# Sheet_02_Arduino_Mega2560.net
KiCad netlist of a schematic drawn in Altium Designer
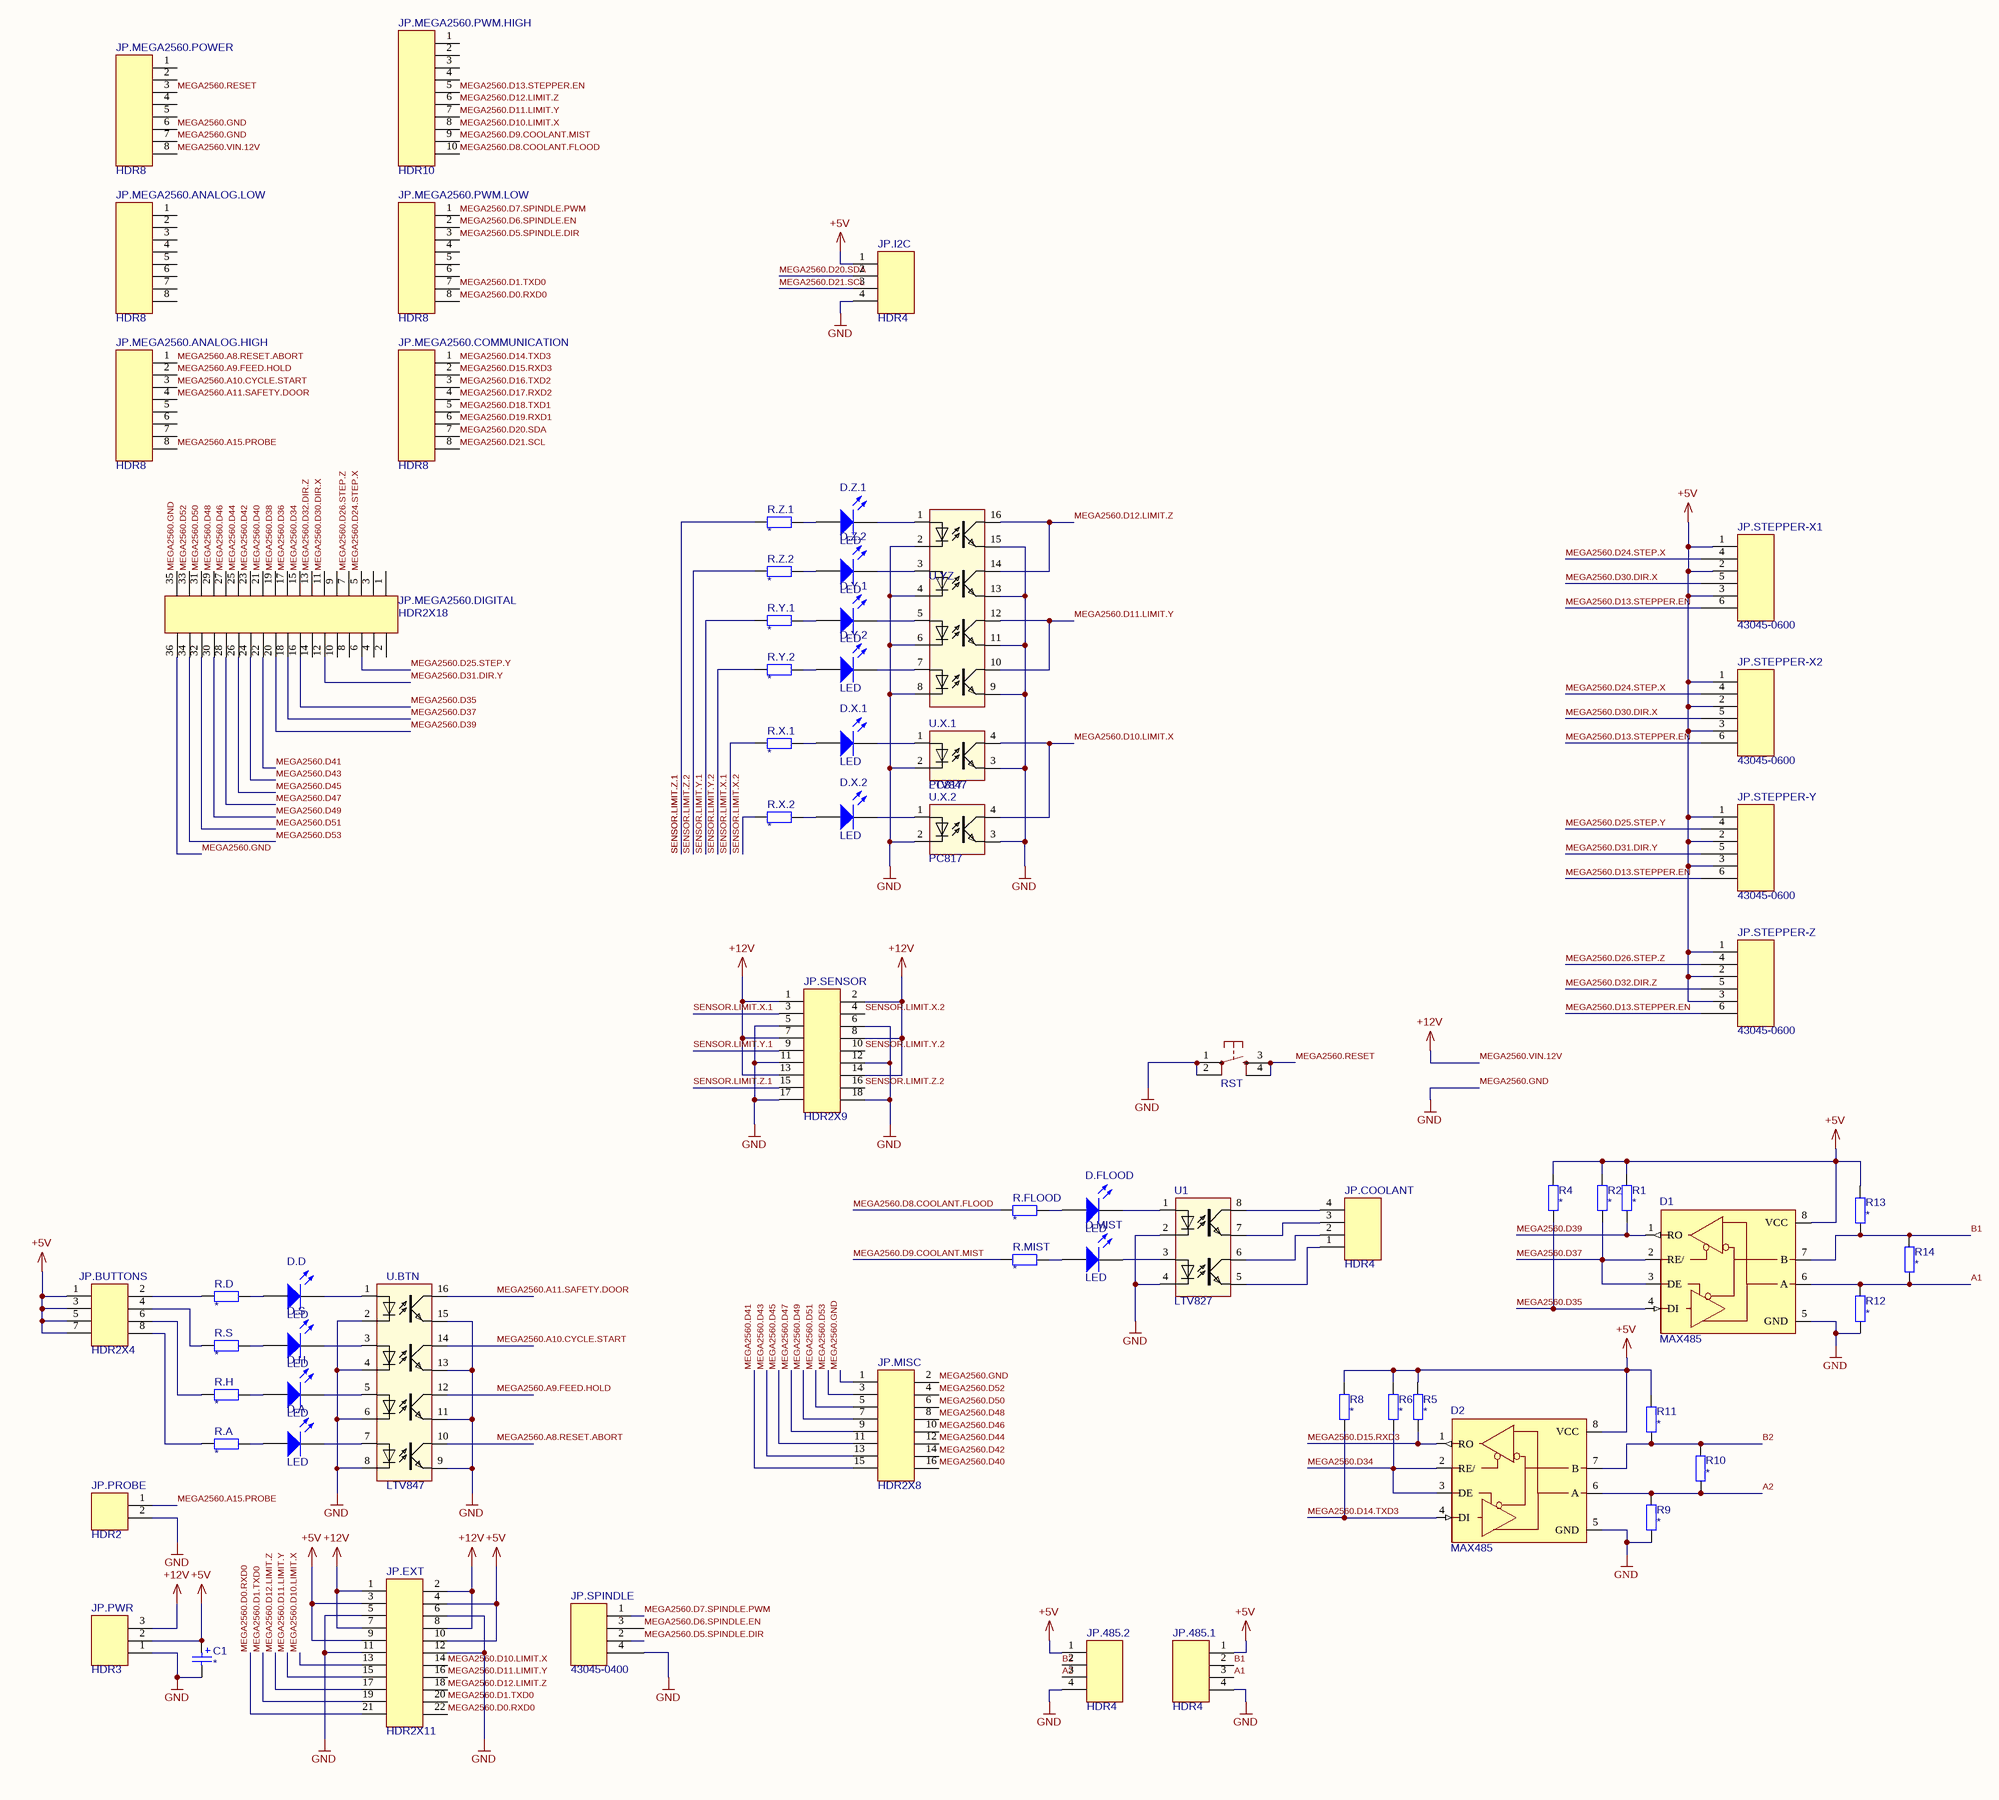
[diagram p0: Sheet.02.Arduino.Mega2560.SchDoc]

(export (version "E")
  (design (tool "Eeschema 10.0.6"))
  (components
    (comp (ref "C1")
      (value "*")
      (footprint "E3,5-8")
      (description "Polarized Capacitor (Radial)")
      (fields (field (name "PUBLISHER") "Altium Limited"))
      (libsource (lib "Net173") (part "CAP.POL"))
    )
    (comp (ref "D.A")
      (value "LED")
      (footprint "1206-SMD-LED")
      (fields (field (name "PUBLISHER") "Altium Limited"))
      (libsource (lib "Net173") (part "LED"))
    )
    (comp (ref "D.D")
      (value "LED")
      (footprint "1206-SMD-LED")
      (fields (field (name "PUBLISHER") "Altium Limited"))
      (libsource (lib "Net173") (part "LED"))
    )
    (comp (ref "D.FLOOD")
      (value "LED")
      (footprint "1206-SMD-LED")
      (fields (field (name "PUBLISHER") "Altium Limited"))
      (libsource (lib "Net173") (part "LED"))
    )
    (comp (ref "D.H")
      (value "LED")
      (footprint "1206-SMD-LED")
      (fields (field (name "PUBLISHER") "Altium Limited"))
      (libsource (lib "Net173") (part "LED"))
    )
    (comp (ref "D.MIST")
      (value "LED")
      (footprint "1206-SMD-LED")
      (fields (field (name "PUBLISHER") "Altium Limited"))
      (libsource (lib "Net173") (part "LED"))
    )
    (comp (ref "D.S")
      (value "LED")
      (footprint "1206-SMD-LED")
      (fields (field (name "PUBLISHER") "Altium Limited"))
      (libsource (lib "Net173") (part "LED"))
    )
    (comp (ref "D.X.1")
      (value "LED")
      (footprint "1206-SMD-LED")
      (fields (field (name "PUBLISHER") "Altium Limited"))
      (libsource (lib "Net173") (part "LED"))
    )
    (comp (ref "D.X.2")
      (value "LED")
      (footprint "1206-SMD-LED")
      (fields (field (name "PUBLISHER") "Altium Limited"))
      (libsource (lib "Net173") (part "LED"))
    )
    (comp (ref "D.Y.1")
      (value "LED")
      (footprint "1206-SMD-LED")
      (fields (field (name "PUBLISHER") "Altium Limited"))
      (libsource (lib "Net173") (part "LED"))
    )
    (comp (ref "D.Y.2")
      (value "LED")
      (footprint "1206-SMD-LED")
      (fields (field (name "PUBLISHER") "Altium Limited"))
      (libsource (lib "Net173") (part "LED"))
    )
    (comp (ref "D.Z.1")
      (value "LED")
      (footprint "1206-SMD-LED")
      (fields (field (name "PUBLISHER") "Altium Limited"))
      (libsource (lib "Net173") (part "LED"))
    )
    (comp (ref "D.Z.2")
      (value "LED")
      (footprint "1206-SMD-LED")
      (fields (field (name "PUBLISHER") "Altium Limited"))
      (libsource (lib "Net173") (part "LED"))
    )
    (comp (ref "D1") (value "MAX485") (footprint "DIP8") (libsource (lib "Net173") (part "MAX485")))
    (comp (ref "D2") (value "MAX485") (footprint "DIP8") (libsource (lib "Net173") (part "MAX485")))
    (comp (ref "JP.485.1") (value "HDR4") (footprint "HDR1X4") (libsource (lib "") (part "HDR4_2")))
    (comp (ref "JP.485.2") (value "HDR4") (footprint "HDR1X4") (libsource (lib "Net173") (part "HDR4")))
    (comp (ref "JP.BUTTONS") (value "HDR2X4") (footprint "HDR2X4") (libsource (lib "Net173") (part "HDR2X4")))
    (comp (ref "JP.COOLANT") (value "HDR4") (footprint "HDR1X4H") (libsource (lib "") (part "HDR4_1")))
    (comp (ref "JP.EXT") (value "HDR2X11") (footprint "HDR2X11") (libsource (lib "Net173") (part "HDR2X11")))
    (comp (ref "JP.I2C") (value "HDR4") (footprint "HDR1X4") (libsource (lib "Net173") (part "HDR4")))
    (comp (ref "JP.MEGA2560.ANALOG.HIGH")
      (value "HDR8")
      (footprint "HDR8-BOTTOM")
      (libsource (lib "Net173") (part "HDR8"))
    )
    (comp (ref "JP.MEGA2560.ANALOG.LOW")
      (value "HDR8")
      (footprint "HDR8-BOTTOM")
      (libsource (lib "Net173") (part "HDR8"))
    )
    (comp (ref "JP.MEGA2560.COMMUNICATION")
      (value "HDR8")
      (footprint "HDR8-BOTTOM")
      (libsource (lib "Net173") (part "HDR8"))
    )
    (comp (ref "JP.MEGA2560.DIGITAL")
      (value "HDR2X18")
      (footprint "HDR2X18-BOTTOM")
      (libsource (lib "Net173") (part "HDR2X18"))
    )
    (comp (ref "JP.MEGA2560.POWER")
      (value "HDR8")
      (footprint "HDR8-BOTTOM")
      (libsource (lib "Net173") (part "HDR8"))
    )
    (comp (ref "JP.MEGA2560.PWM.HIGH")
      (value "HDR10")
      (footprint "HDR10-BOTTOM")
      (libsource (lib "Net173") (part "HDR10"))
    )
    (comp (ref "JP.MEGA2560.PWM.LOW")
      (value "HDR8")
      (footprint "HDR8-BOTTOM")
      (libsource (lib "Net173") (part "HDR8"))
    )
    (comp (ref "JP.MISC") (value "HDR2X8") (footprint "HDR2X8") (libsource (lib "Net173") (part "HDR2X8")))
    (comp (ref "JP.PROBE") (value "HDR2") (footprint "HDR1X2") (libsource (lib "Net173") (part "HDR2")))
    (comp (ref "JP.PWR") (value "HDR3") (footprint "HDR1X3H") (libsource (lib "Net173") (part "HDR3")))
    (comp (ref "JP.SENSOR") (value "HDR2X9") (footprint "HDR2X9") (libsource (lib "Net173") (part "HDR2X9")))
    (comp (ref "JP.SPINDLE")
      (value "43045-0400")
      (footprint "43045-0400")
      (libsource (lib "Net173") (part "43045-0400"))
    )
    (comp (ref "JP.STEPPER-X1")
      (value "43045-0600")
      (footprint "43045-0600")
      (libsource (lib "Net173") (part "43045-0600"))
    )
    (comp (ref "JP.STEPPER-X2")
      (value "43045-0600")
      (footprint "43045-0600")
      (libsource (lib "Net173") (part "43045-0600"))
    )
    (comp (ref "JP.STEPPER-Y")
      (value "43045-0600")
      (footprint "43045-0600")
      (libsource (lib "Net173") (part "43045-0600"))
    )
    (comp (ref "JP.STEPPER-Z")
      (value "43045-0600")
      (footprint "43045-0600")
      (libsource (lib "Net173") (part "43045-0600"))
    )
    (comp (ref "R.A") (value "*") (footprint "1206-SMD-RES") (libsource (lib "") (part "RES_1")))
    (comp (ref "R.D") (value "*") (footprint "1206-SMD-RES") (libsource (lib "") (part "RES_1")))
    (comp (ref "R.FLOOD") (value "*") (footprint "1206-SMD-RES") (libsource (lib "") (part "RES_1")))
    (comp (ref "R.H") (value "*") (footprint "1206-SMD-RES") (libsource (lib "") (part "RES_1")))
    (comp (ref "R.MIST") (value "*") (footprint "1206-SMD-RES") (libsource (lib "") (part "RES_1")))
    (comp (ref "R.S") (value "*") (footprint "1206-SMD-RES") (libsource (lib "") (part "RES_1")))
    (comp (ref "R.X.1") (value "*") (footprint "1206-SMD-RES") (libsource (lib "") (part "RES_1")))
    (comp (ref "R.X.2") (value "*") (footprint "1206-SMD-RES") (libsource (lib "") (part "RES_1")))
    (comp (ref "R.Y.1") (value "*") (footprint "1206-SMD-RES") (libsource (lib "") (part "RES_1")))
    (comp (ref "R.Y.2") (value "*") (footprint "1206-SMD-RES") (libsource (lib "") (part "RES_1")))
    (comp (ref "R.Z.1") (value "*") (footprint "1206-SMD-RES") (libsource (lib "") (part "RES_1")))
    (comp (ref "R.Z.2") (value "*") (footprint "1206-SMD-RES") (libsource (lib "") (part "RES_1")))
    (comp (ref "R1") (value "*") (footprint "1206-SMD-RES") (libsource (lib "Net173") (part "RES")))
    (comp (ref "R2") (value "*") (footprint "1206-SMD-RES") (libsource (lib "Net173") (part "RES")))
    (comp (ref "R4") (value "*") (footprint "1206-SMD-RES") (libsource (lib "Net173") (part "RES")))
    (comp (ref "R5") (value "*") (footprint "1206-SMD-RES") (libsource (lib "Net173") (part "RES")))
    (comp (ref "R6") (value "*") (footprint "1206-SMD-RES") (libsource (lib "Net173") (part "RES")))
    (comp (ref "R8") (value "*") (footprint "1206-SMD-RES") (libsource (lib "Net173") (part "RES")))
    (comp (ref "R9") (value "*") (footprint "1206-SMD-RES") (libsource (lib "Net173") (part "RES")))
    (comp (ref "R10") (value "*") (footprint "1206-SMD-RES") (libsource (lib "Net173") (part "RES")))
    (comp (ref "R11") (value "*") (footprint "1206-SMD-RES") (libsource (lib "Net173") (part "RES")))
    (comp (ref "R12") (value "*") (footprint "1206-SMD-RES") (libsource (lib "Net173") (part "RES")))
    (comp (ref "R13") (value "*") (footprint "1206-SMD-RES") (libsource (lib "Net173") (part "RES")))
    (comp (ref "R14") (value "*") (footprint "1206-SMD-RES") (libsource (lib "Net173") (part "RES")))
    (comp (ref "RST")
      (value "OMRON SWITCH")
      (footprint "B3F-10XX")
      (fields (field (name "MPN") "B3F-1000"))
      (libsource (lib "Net173") (part "B3F-10-XX"))
    )
    (comp (ref "U.BTN") (value "LTV847") (footprint "DIP16") (libsource (lib "Net173") (part "LTV847")))
    (comp (ref "U.X.1") (value "PC817") (footprint "DIP4") (libsource (lib "Net173") (part "PC817")))
    (comp (ref "U.X.2") (value "PC817") (footprint "DIP4") (libsource (lib "Net173") (part "PC817")))
    (comp (ref "U.YZ") (value "LTV847") (footprint "DIP16") (libsource (lib "Net173") (part "LTV847")))
    (comp (ref "U1") (value "LTV827") (footprint "DIP8") (libsource (lib "Net173") (part "LTV827")))
  )
  (nets
    (net (code "1") (name "+5V") (class "Default")
      (node (ref "C1") (pin "+") (pinfunction "1_+") (pintype "passive"))
      (node (ref "D1") (pin "8") (pinfunction "VCC_8") (pintype "power_in"))
      (node (ref "D2") (pin "8") (pinfunction "VCC_8") (pintype "power_in"))
      (node (ref "JP.485.1") (pin "1") (pinfunction "1_1") (pintype "passive"))
      (node (ref "JP.485.2") (pin "1") (pinfunction "1_1") (pintype "passive"))
      (node (ref "JP.BUTTONS") (pin "1") (pinfunction "1_1") (pintype "passive"))
      (node (ref "JP.BUTTONS") (pin "3") (pinfunction "3_3") (pintype "passive"))
      (node (ref "JP.BUTTONS") (pin "5") (pinfunction "5_5") (pintype "passive"))
      (node (ref "JP.BUTTONS") (pin "7") (pinfunction "7_7") (pintype "passive"))
      (node (ref "JP.EXT") (pin "10") (pinfunction "10_10") (pintype "passive"))
      (node (ref "JP.EXT") (pin "3") (pinfunction "3_3") (pintype "passive"))
      (node (ref "JP.EXT") (pin "4") (pinfunction "4_4") (pintype "passive"))
      (node (ref "JP.EXT") (pin "9") (pinfunction "9_9") (pintype "passive"))
      (node (ref "JP.I2C") (pin "1") (pinfunction "1_1") (pintype "passive"))
      (node (ref "JP.PWR") (pin "2") (pinfunction "2_2") (pintype "passive"))
      (node (ref "JP.STEPPER-X1") (pin "1") (pinfunction "1_1") (pintype "passive"))
      (node (ref "JP.STEPPER-X1") (pin "2") (pinfunction "2_2") (pintype "passive"))
      (node (ref "JP.STEPPER-X1") (pin "3") (pinfunction "3_3") (pintype "passive"))
      (node (ref "JP.STEPPER-X2") (pin "1") (pinfunction "1_1") (pintype "passive"))
      (node (ref "JP.STEPPER-X2") (pin "2") (pinfunction "2_2") (pintype "passive"))
      (node (ref "JP.STEPPER-X2") (pin "3") (pinfunction "3_3") (pintype "passive"))
      (node (ref "JP.STEPPER-Y") (pin "1") (pinfunction "1_1") (pintype "passive"))
      (node (ref "JP.STEPPER-Y") (pin "2") (pinfunction "2_2") (pintype "passive"))
      (node (ref "JP.STEPPER-Y") (pin "3") (pinfunction "3_3") (pintype "passive"))
      (node (ref "JP.STEPPER-Z") (pin "1") (pinfunction "1_1") (pintype "passive"))
      (node (ref "JP.STEPPER-Z") (pin "2") (pinfunction "2_2") (pintype "passive"))
      (node (ref "JP.STEPPER-Z") (pin "3") (pinfunction "3_3") (pintype "passive"))
      (node (ref "R1") (pin "2") (pinfunction "2_2") (pintype "passive"))
      (node (ref "R11") (pin "2") (pinfunction "2_2") (pintype "passive"))
      (node (ref "R13") (pin "2") (pinfunction "2_2") (pintype "passive"))
      (node (ref "R2") (pin "2") (pinfunction "2_2") (pintype "passive"))
      (node (ref "R4") (pin "2") (pinfunction "2_2") (pintype "passive"))
      (node (ref "R5") (pin "2") (pinfunction "2_2") (pintype "passive"))
      (node (ref "R6") (pin "2") (pinfunction "2_2") (pintype "passive"))
      (node (ref "R8") (pin "2") (pinfunction "2_2") (pintype "passive"))
    )
    (net (code "2") (name "+12V") (class "Default")
      (node (ref "JP.EXT") (pin "1") (pinfunction "1_1") (pintype "passive"))
      (node (ref "JP.EXT") (pin "2") (pinfunction "2_2") (pintype "passive"))
      (node (ref "JP.EXT") (pin "7") (pinfunction "7_7") (pintype "passive"))
      (node (ref "JP.EXT") (pin "8") (pinfunction "8_8") (pintype "passive"))
      (node (ref "JP.MEGA2560.POWER") (pin "8") (pinfunction "8_8") (pintype "passive"))
      (node (ref "JP.PWR") (pin "3") (pinfunction "3_3") (pintype "passive"))
      (node (ref "JP.SENSOR") (pin "1") (pinfunction "1_1") (pintype "passive"))
      (node (ref "JP.SENSOR") (pin "13") (pinfunction "13_13") (pintype "passive"))
      (node (ref "JP.SENSOR") (pin "14") (pinfunction "14_14") (pintype "passive"))
      (node (ref "JP.SENSOR") (pin "2") (pinfunction "2_2") (pintype "passive"))
      (node (ref "JP.SENSOR") (pin "7") (pinfunction "7_7") (pintype "passive"))
      (node (ref "JP.SENSOR") (pin "8") (pinfunction "8_8") (pintype "passive"))
    )
    (net (code "3") (name "/A1") (class "Default")
      (node (ref "D1") (pin "6") (pinfunction "A_6") (pintype "passive"))
      (node (ref "JP.485.1") (pin "3") (pinfunction "3_3") (pintype "passive"))
      (node (ref "R12") (pin "2") (pinfunction "2_2") (pintype "passive"))
      (node (ref "R14") (pin "1") (pinfunction "1_1") (pintype "passive"))
    )
    (net (code "4") (name "/A2") (class "Default")
      (node (ref "D2") (pin "6") (pinfunction "A_6") (pintype "passive"))
      (node (ref "JP.485.2") (pin "3") (pinfunction "3_3") (pintype "passive"))
      (node (ref "R10") (pin "1") (pinfunction "1_1") (pintype "passive"))
      (node (ref "R9") (pin "2") (pinfunction "2_2") (pintype "passive"))
    )
    (net (code "5") (name "/B1") (class "Default")
      (node (ref "D1") (pin "7") (pinfunction "B_7") (pintype "passive"))
      (node (ref "JP.485.1") (pin "2") (pinfunction "2_2") (pintype "passive"))
      (node (ref "R13") (pin "1") (pinfunction "1_1") (pintype "passive"))
      (node (ref "R14") (pin "2") (pinfunction "2_2") (pintype "passive"))
    )
    (net (code "6") (name "/B2") (class "Default")
      (node (ref "D2") (pin "7") (pinfunction "B_7") (pintype "passive"))
      (node (ref "JP.485.2") (pin "2") (pinfunction "2_2") (pintype "passive"))
      (node (ref "R10") (pin "2") (pinfunction "2_2") (pintype "passive"))
      (node (ref "R11") (pin "1") (pinfunction "1_1") (pintype "passive"))
    )
    (net (code "7") (name "/MEGA2560.A8.RESET.ABORT") (class "Default")
      (node (ref "JP.MEGA2560.ANALOG.HIGH") (pin "1") (pinfunction "1_1") (pintype "passive"))
      (node (ref "U.BTN") (pin "10") (pinfunction "10_10") (pintype "passive"))
    )
    (net (code "8") (name "/MEGA2560.A9.FEED.HOLD") (class "Default")
      (node (ref "JP.MEGA2560.ANALOG.HIGH") (pin "2") (pinfunction "2_2") (pintype "passive"))
      (node (ref "U.BTN") (pin "12") (pinfunction "12_12") (pintype "passive"))
    )
    (net (code "9") (name "/MEGA2560.A10.CYCLE.START") (class "Default")
      (node (ref "JP.MEGA2560.ANALOG.HIGH") (pin "3") (pinfunction "3_3") (pintype "passive"))
      (node (ref "U.BTN") (pin "14") (pinfunction "14_14") (pintype "passive"))
    )
    (net (code "10") (name "/MEGA2560.A11.SAFETY.DOOR") (class "Default")
      (node (ref "JP.MEGA2560.ANALOG.HIGH") (pin "4") (pinfunction "4_4") (pintype "passive"))
      (node (ref "U.BTN") (pin "16") (pinfunction "16_16") (pintype "passive"))
    )
    (net (code "11") (name "/MEGA2560.A15.PROBE") (class "Default")
      (node (ref "JP.MEGA2560.ANALOG.HIGH") (pin "8") (pinfunction "8_8") (pintype "passive"))
      (node (ref "JP.PROBE") (pin "1") (pinfunction "1_1") (pintype "passive"))
    )
    (net (code "12") (name "/MEGA2560.D0.RXD0") (class "Default")
      (node (ref "JP.EXT") (pin "21") (pinfunction "21_21") (pintype "passive"))
      (node (ref "JP.EXT") (pin "22") (pinfunction "22_22") (pintype "passive"))
      (node (ref "JP.MEGA2560.PWM.LOW") (pin "8") (pinfunction "8_8") (pintype "passive"))
    )
    (net (code "13") (name "/MEGA2560.D1.TXD0") (class "Default")
      (node (ref "JP.EXT") (pin "19") (pinfunction "19_19") (pintype "passive"))
      (node (ref "JP.EXT") (pin "20") (pinfunction "20_20") (pintype "passive"))
      (node (ref "JP.MEGA2560.PWM.LOW") (pin "7") (pinfunction "7_7") (pintype "passive"))
    )
    (net (code "14") (name "/MEGA2560.D5.SPINDLE.DIR") (class "Default")
      (node (ref "JP.MEGA2560.PWM.LOW") (pin "3") (pinfunction "3_3") (pintype "passive"))
      (node (ref "JP.SPINDLE") (pin "2") (pinfunction "2_2") (pintype "passive"))
    )
    (net (code "15") (name "/MEGA2560.D6.SPINDLE.EN") (class "Default")
      (node (ref "JP.MEGA2560.PWM.LOW") (pin "2") (pinfunction "2_2") (pintype "passive"))
      (node (ref "JP.SPINDLE") (pin "3") (pinfunction "3_3") (pintype "passive"))
    )
    (net (code "16") (name "/MEGA2560.D7.SPINDLE.PWM") (class "Default")
      (node (ref "JP.MEGA2560.PWM.LOW") (pin "1") (pinfunction "1_1") (pintype "passive"))
      (node (ref "JP.SPINDLE") (pin "1") (pinfunction "1_1") (pintype "passive"))
    )
    (net (code "17") (name "/MEGA2560.D8.COOLANT.FLOOD") (class "Default")
      (node (ref "JP.MEGA2560.PWM.HIGH") (pin "10") (pinfunction "10_10") (pintype "passive"))
      (node (ref "R.FLOOD") (pin "1") (pinfunction "1_1") (pintype "passive"))
    )
    (net (code "18") (name "/MEGA2560.D9.COOLANT.MIST") (class "Default")
      (node (ref "JP.MEGA2560.PWM.HIGH") (pin "9") (pinfunction "9_9") (pintype "passive"))
      (node (ref "R.MIST") (pin "1") (pinfunction "1_1") (pintype "passive"))
    )
    (net (code "19") (name "/MEGA2560.D10.LIMIT.X") (class "Default")
      (node (ref "JP.EXT") (pin "13") (pinfunction "13_13") (pintype "passive"))
      (node (ref "JP.EXT") (pin "14") (pinfunction "14_14") (pintype "passive"))
      (node (ref "JP.MEGA2560.PWM.HIGH") (pin "8") (pinfunction "8_8") (pintype "passive"))
      (node (ref "U.X.1") (pin "4") (pintype "passive"))
      (node (ref "U.X.2") (pin "4") (pintype "passive"))
    )
    (net (code "20") (name "/MEGA2560.D11.LIMIT.Y") (class "Default")
      (node (ref "JP.EXT") (pin "15") (pinfunction "15_15") (pintype "passive"))
      (node (ref "JP.EXT") (pin "16") (pinfunction "16_16") (pintype "passive"))
      (node (ref "JP.MEGA2560.PWM.HIGH") (pin "7") (pinfunction "7_7") (pintype "passive"))
      (node (ref "U.YZ") (pin "10") (pinfunction "10_10") (pintype "passive"))
      (node (ref "U.YZ") (pin "12") (pinfunction "12_12") (pintype "passive"))
    )
    (net (code "21") (name "/MEGA2560.D12.LIMIT.Z") (class "Default")
      (node (ref "JP.EXT") (pin "17") (pinfunction "17_17") (pintype "passive"))
      (node (ref "JP.EXT") (pin "18") (pinfunction "18_18") (pintype "passive"))
      (node (ref "JP.MEGA2560.PWM.HIGH") (pin "6") (pinfunction "6_6") (pintype "passive"))
      (node (ref "U.YZ") (pin "14") (pinfunction "14_14") (pintype "passive"))
      (node (ref "U.YZ") (pin "16") (pinfunction "16_16") (pintype "passive"))
    )
    (net (code "22") (name "/MEGA2560.D13.STEPPER.EN") (class "Default")
      (node (ref "JP.MEGA2560.PWM.HIGH") (pin "5") (pinfunction "5_5") (pintype "passive"))
      (node (ref "JP.STEPPER-X1") (pin "6") (pinfunction "6_6") (pintype "passive"))
      (node (ref "JP.STEPPER-X2") (pin "6") (pinfunction "6_6") (pintype "passive"))
      (node (ref "JP.STEPPER-Y") (pin "6") (pinfunction "6_6") (pintype "passive"))
      (node (ref "JP.STEPPER-Z") (pin "6") (pinfunction "6_6") (pintype "passive"))
    )
    (net (code "23") (name "/MEGA2560.D14.TXD3") (class "Default")
      (node (ref "D2") (pin "4") (pinfunction "DI_4") (pintype "input"))
      (node (ref "JP.MEGA2560.COMMUNICATION") (pin "1") (pinfunction "1_1") (pintype "passive"))
      (node (ref "R8") (pin "1") (pinfunction "1_1") (pintype "passive"))
    )
    (net (code "24") (name "/MEGA2560.D15.RXD3") (class "Default")
      (node (ref "D2") (pin "1") (pinfunction "RO_1") (pintype "output"))
      (node (ref "JP.MEGA2560.COMMUNICATION") (pin "2") (pinfunction "2_2") (pintype "passive"))
      (node (ref "R5") (pin "1") (pinfunction "1_1") (pintype "passive"))
    )
    (net (code "25") (name "/MEGA2560.D16.TXD2") (class "Default")
      (node (ref "JP.MEGA2560.COMMUNICATION") (pin "3") (pinfunction "3_3") (pintype "passive"))
    )
    (net (code "26") (name "/MEGA2560.D17.RXD2") (class "Default")
      (node (ref "JP.MEGA2560.COMMUNICATION") (pin "4") (pinfunction "4_4") (pintype "passive"))
    )
    (net (code "27") (name "/MEGA2560.D18.TXD1") (class "Default")
      (node (ref "JP.MEGA2560.COMMUNICATION") (pin "5") (pinfunction "5_5") (pintype "passive"))
    )
    (net (code "28") (name "/MEGA2560.D19.RXD1") (class "Default")
      (node (ref "JP.MEGA2560.COMMUNICATION") (pin "6") (pinfunction "6_6") (pintype "passive"))
    )
    (net (code "29") (name "/MEGA2560.D20.SDA") (class "Default")
      (node (ref "JP.I2C") (pin "2") (pinfunction "2_2") (pintype "passive"))
      (node (ref "JP.MEGA2560.COMMUNICATION") (pin "7") (pinfunction "7_7") (pintype "passive"))
    )
    (net (code "30") (name "/MEGA2560.D21.SCL") (class "Default")
      (node (ref "JP.I2C") (pin "3") (pinfunction "3_3") (pintype "passive"))
      (node (ref "JP.MEGA2560.COMMUNICATION") (pin "8") (pinfunction "8_8") (pintype "passive"))
    )
    (net (code "31") (name "/MEGA2560.D24.STEP.X") (class "Default")
      (node (ref "JP.MEGA2560.DIGITAL") (pin "5") (pinfunction "5_5") (pintype "passive"))
      (node (ref "JP.STEPPER-X1") (pin "4") (pinfunction "4_4") (pintype "passive"))
      (node (ref "JP.STEPPER-X2") (pin "4") (pinfunction "4_4") (pintype "passive"))
    )
    (net (code "32") (name "/MEGA2560.D25.STEP.Y") (class "Default")
      (node (ref "JP.MEGA2560.DIGITAL") (pin "6") (pinfunction "6_6") (pintype "passive"))
      (node (ref "JP.STEPPER-Y") (pin "4") (pinfunction "4_4") (pintype "passive"))
    )
    (net (code "33") (name "/MEGA2560.D26.STEP.Z") (class "Default")
      (node (ref "JP.MEGA2560.DIGITAL") (pin "7") (pinfunction "7_7") (pintype "passive"))
      (node (ref "JP.STEPPER-Z") (pin "4") (pinfunction "4_4") (pintype "passive"))
    )
    (net (code "34") (name "/MEGA2560.D30.DIR.X") (class "Default")
      (node (ref "JP.MEGA2560.DIGITAL") (pin "11") (pinfunction "11_11") (pintype "passive"))
      (node (ref "JP.STEPPER-X1") (pin "5") (pinfunction "5_5") (pintype "passive"))
      (node (ref "JP.STEPPER-X2") (pin "5") (pinfunction "5_5") (pintype "passive"))
    )
    (net (code "35") (name "/MEGA2560.D31.DIR.Y") (class "Default")
      (node (ref "JP.MEGA2560.DIGITAL") (pin "12") (pinfunction "12_12") (pintype "passive"))
      (node (ref "JP.STEPPER-Y") (pin "5") (pinfunction "5_5") (pintype "passive"))
    )
    (net (code "36") (name "/MEGA2560.D32.DIR.Z") (class "Default")
      (node (ref "JP.MEGA2560.DIGITAL") (pin "13") (pinfunction "13_13") (pintype "passive"))
      (node (ref "JP.STEPPER-Z") (pin "5") (pinfunction "5_5") (pintype "passive"))
    )
    (net (code "37") (name "/MEGA2560.D34") (class "Default")
      (node (ref "D2") (pin "2") (pinfunction "RE/_2") (pintype "passive"))
      (node (ref "D2") (pin "3") (pinfunction "DE_3") (pintype "passive"))
      (node (ref "JP.MEGA2560.DIGITAL") (pin "15") (pinfunction "15_15") (pintype "passive"))
      (node (ref "R6") (pin "1") (pinfunction "1_1") (pintype "passive"))
    )
    (net (code "38") (name "/MEGA2560.D35") (class "Default")
      (node (ref "D1") (pin "4") (pinfunction "DI_4") (pintype "input"))
      (node (ref "JP.MEGA2560.DIGITAL") (pin "16") (pinfunction "16_16") (pintype "passive"))
      (node (ref "R4") (pin "1") (pinfunction "1_1") (pintype "passive"))
    )
    (net (code "39") (name "/MEGA2560.D36") (class "Default")
      (node (ref "JP.MEGA2560.DIGITAL") (pin "17") (pinfunction "17_17") (pintype "passive"))
    )
    (net (code "40") (name "/MEGA2560.D37") (class "Default")
      (node (ref "D1") (pin "2") (pinfunction "RE/_2") (pintype "passive"))
      (node (ref "D1") (pin "3") (pinfunction "DE_3") (pintype "passive"))
      (node (ref "JP.MEGA2560.DIGITAL") (pin "18") (pinfunction "18_18") (pintype "passive"))
      (node (ref "R2") (pin "1") (pinfunction "1_1") (pintype "passive"))
    )
    (net (code "41") (name "/MEGA2560.D38") (class "Default")
      (node (ref "JP.MEGA2560.DIGITAL") (pin "19") (pinfunction "19_19") (pintype "passive"))
    )
    (net (code "42") (name "/MEGA2560.D39") (class "Default")
      (node (ref "D1") (pin "1") (pinfunction "RO_1") (pintype "output"))
      (node (ref "JP.MEGA2560.DIGITAL") (pin "20") (pinfunction "20_20") (pintype "passive"))
      (node (ref "R1") (pin "1") (pinfunction "1_1") (pintype "passive"))
    )
    (net (code "43") (name "/MEGA2560.D40") (class "Default")
      (node (ref "JP.MEGA2560.DIGITAL") (pin "21") (pinfunction "21_21") (pintype "passive"))
      (node (ref "JP.MISC") (pin "16") (pinfunction "16_16") (pintype "passive"))
    )
    (net (code "44") (name "/MEGA2560.D41") (class "Default")
      (node (ref "JP.MEGA2560.DIGITAL") (pin "22") (pinfunction "22_22") (pintype "passive"))
      (node (ref "JP.MISC") (pin "15") (pinfunction "15_15") (pintype "passive"))
    )
    (net (code "45") (name "/MEGA2560.D42") (class "Default")
      (node (ref "JP.MEGA2560.DIGITAL") (pin "23") (pinfunction "23_23") (pintype "passive"))
      (node (ref "JP.MISC") (pin "14") (pinfunction "14_14") (pintype "passive"))
    )
    (net (code "46") (name "/MEGA2560.D43") (class "Default")
      (node (ref "JP.MEGA2560.DIGITAL") (pin "24") (pinfunction "24_24") (pintype "passive"))
      (node (ref "JP.MISC") (pin "13") (pinfunction "13_13") (pintype "passive"))
    )
    (net (code "47") (name "/MEGA2560.D44") (class "Default")
      (node (ref "JP.MEGA2560.DIGITAL") (pin "25") (pinfunction "25_25") (pintype "passive"))
      (node (ref "JP.MISC") (pin "12") (pinfunction "12_12") (pintype "passive"))
    )
    (net (code "48") (name "/MEGA2560.D45") (class "Default")
      (node (ref "JP.MEGA2560.DIGITAL") (pin "26") (pinfunction "26_26") (pintype "passive"))
      (node (ref "JP.MISC") (pin "11") (pinfunction "11_11") (pintype "passive"))
    )
    (net (code "49") (name "/MEGA2560.D46") (class "Default")
      (node (ref "JP.MEGA2560.DIGITAL") (pin "27") (pinfunction "27_27") (pintype "passive"))
      (node (ref "JP.MISC") (pin "10") (pinfunction "10_10") (pintype "passive"))
    )
    (net (code "50") (name "/MEGA2560.D47") (class "Default")
      (node (ref "JP.MEGA2560.DIGITAL") (pin "28") (pinfunction "28_28") (pintype "passive"))
      (node (ref "JP.MISC") (pin "9") (pinfunction "9_9") (pintype "passive"))
    )
    (net (code "51") (name "/MEGA2560.D48") (class "Default")
      (node (ref "JP.MEGA2560.DIGITAL") (pin "29") (pinfunction "29_29") (pintype "passive"))
      (node (ref "JP.MISC") (pin "8") (pinfunction "8_8") (pintype "passive"))
    )
    (net (code "52") (name "/MEGA2560.D49") (class "Default")
      (node (ref "JP.MEGA2560.DIGITAL") (pin "30") (pinfunction "30_30") (pintype "passive"))
      (node (ref "JP.MISC") (pin "7") (pinfunction "7_7") (pintype "passive"))
    )
    (net (code "53") (name "/MEGA2560.D50") (class "Default")
      (node (ref "JP.MEGA2560.DIGITAL") (pin "31") (pinfunction "31_31") (pintype "passive"))
      (node (ref "JP.MISC") (pin "6") (pinfunction "6_6") (pintype "passive"))
    )
    (net (code "54") (name "/MEGA2560.D51") (class "Default")
      (node (ref "JP.MEGA2560.DIGITAL") (pin "32") (pinfunction "32_32") (pintype "passive"))
      (node (ref "JP.MISC") (pin "5") (pinfunction "5_5") (pintype "passive"))
    )
    (net (code "55") (name "/MEGA2560.D52") (class "Default")
      (node (ref "JP.MEGA2560.DIGITAL") (pin "33") (pinfunction "33_33") (pintype "passive"))
      (node (ref "JP.MISC") (pin "4") (pinfunction "4_4") (pintype "passive"))
    )
    (net (code "56") (name "/MEGA2560.D53") (class "Default")
      (node (ref "JP.MEGA2560.DIGITAL") (pin "34") (pinfunction "34_34") (pintype "passive"))
      (node (ref "JP.MISC") (pin "3") (pinfunction "3_3") (pintype "passive"))
    )
    (net (code "57") (name "/MEGA2560.RESET") (class "Default")
      (node (ref "JP.MEGA2560.POWER") (pin "3") (pinfunction "3_3") (pintype "passive"))
      (node (ref "RST") (pin "3") (pinfunction "P_3") (pintype "passive"))
      (node (ref "RST") (pin "4") (pinfunction "P1_4") (pintype "passive"))
    )
    (net (code "58") (name "/SENSOR.LIMIT.X.1") (class "Default")
      (node (ref "JP.SENSOR") (pin "3") (pinfunction "3_3") (pintype "passive"))
      (node (ref "R.X.1") (pin "1") (pinfunction "1_1") (pintype "passive"))
    )
    (net (code "59") (name "/SENSOR.LIMIT.X.2") (class "Default")
      (node (ref "JP.SENSOR") (pin "4") (pinfunction "4_4") (pintype "passive"))
      (node (ref "R.X.2") (pin "1") (pinfunction "1_1") (pintype "passive"))
    )
    (net (code "60") (name "/SENSOR.LIMIT.Y.1") (class "Default")
      (node (ref "JP.SENSOR") (pin "9") (pinfunction "9_9") (pintype "passive"))
      (node (ref "R.Y.1") (pin "1") (pinfunction "1_1") (pintype "passive"))
    )
    (net (code "61") (name "/SENSOR.LIMIT.Y.2") (class "Default")
      (node (ref "JP.SENSOR") (pin "10") (pinfunction "10_10") (pintype "passive"))
      (node (ref "R.Y.2") (pin "1") (pinfunction "1_1") (pintype "passive"))
    )
    (net (code "62") (name "/SENSOR.LIMIT.Z.1") (class "Default")
      (node (ref "JP.SENSOR") (pin "15") (pinfunction "15_15") (pintype "passive"))
      (node (ref "R.Z.1") (pin "1") (pinfunction "1_1") (pintype "passive"))
    )
    (net (code "63") (name "/SENSOR.LIMIT.Z.2") (class "Default")
      (node (ref "JP.SENSOR") (pin "16") (pinfunction "16_16") (pintype "passive"))
      (node (ref "R.Z.2") (pin "1") (pinfunction "1_1") (pintype "passive"))
    )
    (net (code "64") (name "GND") (class "Default")
      (node (ref "C1") (pin "-") (pinfunction "2_-") (pintype "passive"))
      (node (ref "D1") (pin "5") (pinfunction "GND_5") (pintype "power_in"))
      (node (ref "D2") (pin "5") (pinfunction "GND_5") (pintype "power_in"))
      (node (ref "JP.485.1") (pin "4") (pinfunction "4_4") (pintype "passive"))
      (node (ref "JP.485.2") (pin "4") (pinfunction "4_4") (pintype "passive"))
      (node (ref "JP.EXT") (pin "11") (pinfunction "11_11") (pintype "passive"))
      (node (ref "JP.EXT") (pin "12") (pinfunction "12_12") (pintype "passive"))
      (node (ref "JP.EXT") (pin "5") (pinfunction "5_5") (pintype "passive"))
      (node (ref "JP.EXT") (pin "6") (pinfunction "6_6") (pintype "passive"))
      (node (ref "JP.I2C") (pin "4") (pinfunction "4_4") (pintype "passive"))
      (node (ref "JP.MEGA2560.DIGITAL") (pin "35") (pinfunction "35_35") (pintype "passive"))
      (node (ref "JP.MEGA2560.DIGITAL") (pin "36") (pinfunction "36_36") (pintype "passive"))
      (node (ref "JP.MEGA2560.POWER") (pin "6") (pinfunction "6_6") (pintype "passive"))
      (node (ref "JP.MEGA2560.POWER") (pin "7") (pinfunction "7_7") (pintype "passive"))
      (node (ref "JP.MISC") (pin "1") (pinfunction "1_1") (pintype "passive"))
      (node (ref "JP.MISC") (pin "2") (pinfunction "2_2") (pintype "passive"))
      (node (ref "JP.PROBE") (pin "2") (pinfunction "2_2") (pintype "passive"))
      (node (ref "JP.PWR") (pin "1") (pinfunction "1_1") (pintype "passive"))
      (node (ref "JP.SENSOR") (pin "11") (pinfunction "11_11") (pintype "passive"))
      (node (ref "JP.SENSOR") (pin "12") (pinfunction "12_12") (pintype "passive"))
      (node (ref "JP.SENSOR") (pin "17") (pinfunction "17_17") (pintype "passive"))
      (node (ref "JP.SENSOR") (pin "18") (pinfunction "18_18") (pintype "passive"))
      (node (ref "JP.SENSOR") (pin "5") (pinfunction "5_5") (pintype "passive"))
      (node (ref "JP.SENSOR") (pin "6") (pinfunction "6_6") (pintype "passive"))
      (node (ref "JP.SPINDLE") (pin "4") (pinfunction "4_4") (pintype "passive"))
      (node (ref "R12") (pin "1") (pinfunction "1_1") (pintype "passive"))
      (node (ref "R9") (pin "1") (pinfunction "1_1") (pintype "passive"))
      (node (ref "RST") (pin "1") (pinfunction "S_1") (pintype "passive"))
      (node (ref "RST") (pin "2") (pinfunction "S1_2") (pintype "passive"))
      (node (ref "U.BTN") (pin "11") (pinfunction "11_11") (pintype "passive"))
      (node (ref "U.BTN") (pin "13") (pinfunction "13_13") (pintype "passive"))
      (node (ref "U.BTN") (pin "15") (pinfunction "15_15") (pintype "passive"))
      (node (ref "U.BTN") (pin "2") (pintype "passive"))
      (node (ref "U.BTN") (pin "4") (pinfunction "4_4") (pintype "passive"))
      (node (ref "U.BTN") (pin "6") (pinfunction "6_6") (pintype "passive"))
      (node (ref "U.BTN") (pin "8") (pinfunction "8_8") (pintype "passive"))
      (node (ref "U.BTN") (pin "9") (pinfunction "9_9") (pintype "passive"))
      (node (ref "U.X.1") (pin "2") (pintype "passive"))
      (node (ref "U.X.1") (pin "3") (pintype "passive"))
      (node (ref "U.X.2") (pin "2") (pintype "passive"))
      (node (ref "U.X.2") (pin "3") (pintype "passive"))
      (node (ref "U.YZ") (pin "11") (pinfunction "11_11") (pintype "passive"))
      (node (ref "U.YZ") (pin "13") (pinfunction "13_13") (pintype "passive"))
      (node (ref "U.YZ") (pin "15") (pinfunction "15_15") (pintype "passive"))
      (node (ref "U.YZ") (pin "2") (pintype "passive"))
      (node (ref "U.YZ") (pin "4") (pinfunction "4_4") (pintype "passive"))
      (node (ref "U.YZ") (pin "6") (pinfunction "6_6") (pintype "passive"))
      (node (ref "U.YZ") (pin "8") (pinfunction "8_8") (pintype "passive"))
      (node (ref "U.YZ") (pin "9") (pinfunction "9_9") (pintype "passive"))
      (node (ref "U1") (pin "2") (pintype "passive"))
      (node (ref "U1") (pin "4") (pinfunction "4_4") (pintype "passive"))
    )
    (net (code "65") (name "Net-(D.A-A)") (class "Default")
      (node (ref "D.A") (pin "1") (pinfunction "A_1") (pintype "passive"))
      (node (ref "R.A") (pin "2") (pinfunction "2_2") (pintype "passive"))
    )
    (net (code "66") (name "Net-(D.A-K)") (class "Default")
      (node (ref "D.A") (pin "2") (pinfunction "K_2") (pintype "passive"))
      (node (ref "U.BTN") (pin "7") (pinfunction "7_7") (pintype "passive"))
    )
    (net (code "67") (name "Net-(D.D-A)") (class "Default")
      (node (ref "D.D") (pin "1") (pinfunction "A_1") (pintype "passive"))
      (node (ref "R.D") (pin "2") (pinfunction "2_2") (pintype "passive"))
    )
    (net (code "68") (name "Net-(D.D-K)") (class "Default")
      (node (ref "D.D") (pin "2") (pinfunction "K_2") (pintype "passive"))
      (node (ref "U.BTN") (pin "1") (pintype "passive"))
    )
    (net (code "69") (name "Net-(D.FLOOD-A)") (class "Default")
      (node (ref "D.FLOOD") (pin "1") (pinfunction "A_1") (pintype "passive"))
      (node (ref "R.FLOOD") (pin "2") (pinfunction "2_2") (pintype "passive"))
    )
    (net (code "70") (name "Net-(D.FLOOD-K)") (class "Default")
      (node (ref "D.FLOOD") (pin "2") (pinfunction "K_2") (pintype "passive"))
      (node (ref "U1") (pin "1") (pintype "passive"))
    )
    (net (code "71") (name "Net-(D.H-A)") (class "Default")
      (node (ref "D.H") (pin "1") (pinfunction "A_1") (pintype "passive"))
      (node (ref "R.H") (pin "2") (pinfunction "2_2") (pintype "passive"))
    )
    (net (code "72") (name "Net-(D.H-K)") (class "Default")
      (node (ref "D.H") (pin "2") (pinfunction "K_2") (pintype "passive"))
      (node (ref "U.BTN") (pin "5") (pinfunction "5_5") (pintype "passive"))
    )
    (net (code "73") (name "Net-(D.MIST-A)") (class "Default")
      (node (ref "D.MIST") (pin "1") (pinfunction "A_1") (pintype "passive"))
      (node (ref "R.MIST") (pin "2") (pinfunction "2_2") (pintype "passive"))
    )
    (net (code "74") (name "Net-(D.MIST-K)") (class "Default")
      (node (ref "D.MIST") (pin "2") (pinfunction "K_2") (pintype "passive"))
      (node (ref "U1") (pin "3") (pinfunction "3_3") (pintype "passive"))
    )
    (net (code "75") (name "Net-(D.S-A)") (class "Default")
      (node (ref "D.S") (pin "1") (pinfunction "A_1") (pintype "passive"))
      (node (ref "R.S") (pin "2") (pinfunction "2_2") (pintype "passive"))
    )
    (net (code "76") (name "Net-(D.S-K)") (class "Default")
      (node (ref "D.S") (pin "2") (pinfunction "K_2") (pintype "passive"))
      (node (ref "U.BTN") (pin "3") (pinfunction "3_3") (pintype "passive"))
    )
    (net (code "77") (name "Net-(D.X.1-A)") (class "Default")
      (node (ref "D.X.1") (pin "1") (pinfunction "A_1") (pintype "passive"))
      (node (ref "R.X.1") (pin "2") (pinfunction "2_2") (pintype "passive"))
    )
    (net (code "78") (name "Net-(D.X.1-K)") (class "Default")
      (node (ref "D.X.1") (pin "2") (pinfunction "K_2") (pintype "passive"))
      (node (ref "U.X.1") (pin "1") (pintype "passive"))
    )
    (net (code "79") (name "Net-(D.X.2-A)") (class "Default")
      (node (ref "D.X.2") (pin "1") (pinfunction "A_1") (pintype "passive"))
      (node (ref "R.X.2") (pin "2") (pinfunction "2_2") (pintype "passive"))
    )
    (net (code "80") (name "Net-(D.X.2-K)") (class "Default")
      (node (ref "D.X.2") (pin "2") (pinfunction "K_2") (pintype "passive"))
      (node (ref "U.X.2") (pin "1") (pintype "passive"))
    )
    (net (code "81") (name "Net-(D.Y.1-A)") (class "Default")
      (node (ref "D.Y.1") (pin "1") (pinfunction "A_1") (pintype "passive"))
      (node (ref "R.Y.1") (pin "2") (pinfunction "2_2") (pintype "passive"))
    )
    (net (code "82") (name "Net-(D.Y.1-K)") (class "Default")
      (node (ref "D.Y.1") (pin "2") (pinfunction "K_2") (pintype "passive"))
      (node (ref "U.YZ") (pin "5") (pinfunction "5_5") (pintype "passive"))
    )
    (net (code "83") (name "Net-(D.Y.2-A)") (class "Default")
      (node (ref "D.Y.2") (pin "1") (pinfunction "A_1") (pintype "passive"))
      (node (ref "R.Y.2") (pin "2") (pinfunction "2_2") (pintype "passive"))
    )
    (net (code "84") (name "Net-(D.Y.2-K)") (class "Default")
      (node (ref "D.Y.2") (pin "2") (pinfunction "K_2") (pintype "passive"))
      (node (ref "U.YZ") (pin "7") (pinfunction "7_7") (pintype "passive"))
    )
    (net (code "85") (name "Net-(D.Z.1-A)") (class "Default")
      (node (ref "D.Z.1") (pin "1") (pinfunction "A_1") (pintype "passive"))
      (node (ref "R.Z.1") (pin "2") (pinfunction "2_2") (pintype "passive"))
    )
    (net (code "86") (name "Net-(D.Z.1-K)") (class "Default")
      (node (ref "D.Z.1") (pin "2") (pinfunction "K_2") (pintype "passive"))
      (node (ref "U.YZ") (pin "1") (pintype "passive"))
    )
    (net (code "87") (name "Net-(D.Z.2-A)") (class "Default")
      (node (ref "D.Z.2") (pin "1") (pinfunction "A_1") (pintype "passive"))
      (node (ref "R.Z.2") (pin "2") (pinfunction "2_2") (pintype "passive"))
    )
    (net (code "88") (name "Net-(D.Z.2-K)") (class "Default")
      (node (ref "D.Z.2") (pin "2") (pinfunction "K_2") (pintype "passive"))
      (node (ref "U.YZ") (pin "3") (pinfunction "3_3") (pintype "passive"))
    )
    (net (code "89") (name "Net-(JP.BUTTONS-Pad2)") (class "Default")
      (node (ref "JP.BUTTONS") (pin "2") (pinfunction "2_2") (pintype "passive"))
      (node (ref "R.D") (pin "1") (pinfunction "1_1") (pintype "passive"))
    )
    (net (code "90") (name "Net-(JP.BUTTONS-Pad4)") (class "Default")
      (node (ref "JP.BUTTONS") (pin "4") (pinfunction "4_4") (pintype "passive"))
      (node (ref "R.S") (pin "1") (pinfunction "1_1") (pintype "passive"))
    )
    (net (code "91") (name "Net-(JP.BUTTONS-Pad6)") (class "Default")
      (node (ref "JP.BUTTONS") (pin "6") (pinfunction "6_6") (pintype "passive"))
      (node (ref "R.H") (pin "1") (pinfunction "1_1") (pintype "passive"))
    )
    (net (code "92") (name "Net-(JP.BUTTONS-Pad8)") (class "Default")
      (node (ref "JP.BUTTONS") (pin "8") (pinfunction "8_8") (pintype "passive"))
      (node (ref "R.A") (pin "1") (pinfunction "1_1") (pintype "passive"))
    )
    (net (code "93") (name "Net-(JP.COOLANT-Pad1)") (class "Default")
      (node (ref "JP.COOLANT") (pin "1") (pinfunction "1_1") (pintype "passive"))
      (node (ref "U1") (pin "5") (pinfunction "5_5") (pintype "passive"))
    )
    (net (code "94") (name "Net-(JP.COOLANT-Pad2)") (class "Default")
      (node (ref "JP.COOLANT") (pin "2") (pinfunction "2_2") (pintype "passive"))
      (node (ref "U1") (pin "6") (pinfunction "6_6") (pintype "passive"))
    )
    (net (code "95") (name "Net-(JP.COOLANT-Pad3)") (class "Default")
      (node (ref "JP.COOLANT") (pin "3") (pinfunction "3_3") (pintype "passive"))
      (node (ref "U1") (pin "7") (pinfunction "7_7") (pintype "passive"))
    )
    (net (code "96") (name "Net-(JP.COOLANT-Pad4)") (class "Default")
      (node (ref "JP.COOLANT") (pin "4") (pinfunction "4_4") (pintype "passive"))
      (node (ref "U1") (pin "8") (pinfunction "8_8") (pintype "passive"))
    )
    (net (code "97") (name "unconnected-(JP.MEGA2560.ANALOG.HIGH-Pad5)") (class "Default")
      (node (ref "JP.MEGA2560.ANALOG.HIGH") (pin "5") (pinfunction "5_5") (pintype "passive"))
    )
    (net (code "98") (name "unconnected-(JP.MEGA2560.ANALOG.HIGH-Pad6)") (class "Default")
      (node (ref "JP.MEGA2560.ANALOG.HIGH") (pin "6") (pinfunction "6_6") (pintype "passive"))
    )
    (net (code "99") (name "unconnected-(JP.MEGA2560.ANALOG.HIGH-Pad7)") (class "Default")
      (node (ref "JP.MEGA2560.ANALOG.HIGH") (pin "7") (pinfunction "7_7") (pintype "passive"))
    )
    (net (code "100") (name "unconnected-(JP.MEGA2560.ANALOG.LOW-Pad1)") (class "Default")
      (node (ref "JP.MEGA2560.ANALOG.LOW") (pin "1") (pinfunction "1_1") (pintype "passive"))
    )
    (net (code "101") (name "unconnected-(JP.MEGA2560.ANALOG.LOW-Pad2)") (class "Default")
      (node (ref "JP.MEGA2560.ANALOG.LOW") (pin "2") (pinfunction "2_2") (pintype "passive"))
    )
    (net (code "102") (name "unconnected-(JP.MEGA2560.ANALOG.LOW-Pad3)") (class "Default")
      (node (ref "JP.MEGA2560.ANALOG.LOW") (pin "3") (pinfunction "3_3") (pintype "passive"))
    )
    (net (code "103") (name "unconnected-(JP.MEGA2560.ANALOG.LOW-Pad4)") (class "Default")
      (node (ref "JP.MEGA2560.ANALOG.LOW") (pin "4") (pinfunction "4_4") (pintype "passive"))
    )
    (net (code "104") (name "unconnected-(JP.MEGA2560.ANALOG.LOW-Pad5)") (class "Default")
      (node (ref "JP.MEGA2560.ANALOG.LOW") (pin "5") (pinfunction "5_5") (pintype "passive"))
    )
    (net (code "105") (name "unconnected-(JP.MEGA2560.ANALOG.LOW-Pad6)") (class "Default")
      (node (ref "JP.MEGA2560.ANALOG.LOW") (pin "6") (pinfunction "6_6") (pintype "passive"))
    )
    (net (code "106") (name "unconnected-(JP.MEGA2560.ANALOG.LOW-Pad7)") (class "Default")
      (node (ref "JP.MEGA2560.ANALOG.LOW") (pin "7") (pinfunction "7_7") (pintype "passive"))
    )
    (net (code "107") (name "unconnected-(JP.MEGA2560.ANALOG.LOW-Pad8)") (class "Default")
      (node (ref "JP.MEGA2560.ANALOG.LOW") (pin "8") (pinfunction "8_8") (pintype "passive"))
    )
    (net (code "108") (name "unconnected-(JP.MEGA2560.DIGITAL-Pad1)") (class "Default")
      (node (ref "JP.MEGA2560.DIGITAL") (pin "1") (pinfunction "1_1") (pintype "passive"))
    )
    (net (code "109") (name "unconnected-(JP.MEGA2560.DIGITAL-Pad2)") (class "Default")
      (node (ref "JP.MEGA2560.DIGITAL") (pin "2") (pinfunction "2_2") (pintype "passive"))
    )
    (net (code "110") (name "unconnected-(JP.MEGA2560.DIGITAL-Pad3)") (class "Default")
      (node (ref "JP.MEGA2560.DIGITAL") (pin "3") (pinfunction "3_3") (pintype "passive"))
    )
    (net (code "111") (name "unconnected-(JP.MEGA2560.DIGITAL-Pad4)") (class "Default")
      (node (ref "JP.MEGA2560.DIGITAL") (pin "4") (pinfunction "4_4") (pintype "passive"))
    )
    (net (code "112") (name "unconnected-(JP.MEGA2560.DIGITAL-Pad8)") (class "Default")
      (node (ref "JP.MEGA2560.DIGITAL") (pin "8") (pinfunction "8_8") (pintype "passive"))
    )
    (net (code "113") (name "unconnected-(JP.MEGA2560.DIGITAL-Pad9)") (class "Default")
      (node (ref "JP.MEGA2560.DIGITAL") (pin "9") (pinfunction "9_9") (pintype "passive"))
    )
    (net (code "114") (name "unconnected-(JP.MEGA2560.DIGITAL-Pad10)") (class "Default")
      (node (ref "JP.MEGA2560.DIGITAL") (pin "10") (pinfunction "10_10") (pintype "passive"))
    )
    (net (code "115") (name "unconnected-(JP.MEGA2560.DIGITAL-Pad14)") (class "Default")
      (node (ref "JP.MEGA2560.DIGITAL") (pin "14") (pinfunction "14_14") (pintype "passive"))
    )
    (net (code "116") (name "unconnected-(JP.MEGA2560.POWER-Pad1)") (class "Default")
      (node (ref "JP.MEGA2560.POWER") (pin "1") (pinfunction "1_1") (pintype "passive"))
    )
    (net (code "117") (name "unconnected-(JP.MEGA2560.POWER-Pad2)") (class "Default")
      (node (ref "JP.MEGA2560.POWER") (pin "2") (pinfunction "2_2") (pintype "passive"))
    )
    (net (code "118") (name "unconnected-(JP.MEGA2560.POWER-Pad4)") (class "Default")
      (node (ref "JP.MEGA2560.POWER") (pin "4") (pinfunction "4_4") (pintype "passive"))
    )
    (net (code "119") (name "unconnected-(JP.MEGA2560.POWER-Pad5)") (class "Default")
      (node (ref "JP.MEGA2560.POWER") (pin "5") (pinfunction "5_5") (pintype "passive"))
    )
    (net (code "120") (name "unconnected-(JP.MEGA2560.PWM.HIGH-Pad1)") (class "Default")
      (node (ref "JP.MEGA2560.PWM.HIGH") (pin "1") (pinfunction "1_1") (pintype "passive"))
    )
    (net (code "121") (name "unconnected-(JP.MEGA2560.PWM.HIGH-Pad2)") (class "Default")
      (node (ref "JP.MEGA2560.PWM.HIGH") (pin "2") (pinfunction "2_2") (pintype "passive"))
    )
    (net (code "122") (name "unconnected-(JP.MEGA2560.PWM.HIGH-Pad3)") (class "Default")
      (node (ref "JP.MEGA2560.PWM.HIGH") (pin "3") (pinfunction "3_3") (pintype "passive"))
    )
    (net (code "123") (name "unconnected-(JP.MEGA2560.PWM.HIGH-Pad4)") (class "Default")
      (node (ref "JP.MEGA2560.PWM.HIGH") (pin "4") (pinfunction "4_4") (pintype "passive"))
    )
    (net (code "124") (name "unconnected-(JP.MEGA2560.PWM.LOW-Pad4)") (class "Default")
      (node (ref "JP.MEGA2560.PWM.LOW") (pin "4") (pinfunction "4_4") (pintype "passive"))
    )
    (net (code "125") (name "unconnected-(JP.MEGA2560.PWM.LOW-Pad5)") (class "Default")
      (node (ref "JP.MEGA2560.PWM.LOW") (pin "5") (pinfunction "5_5") (pintype "passive"))
    )
    (net (code "126") (name "unconnected-(JP.MEGA2560.PWM.LOW-Pad6)") (class "Default")
      (node (ref "JP.MEGA2560.PWM.LOW") (pin "6") (pinfunction "6_6") (pintype "passive"))
    )
  )
)
